# Misc.net
KiCad netlist of a schematic drawn in Altium Designer
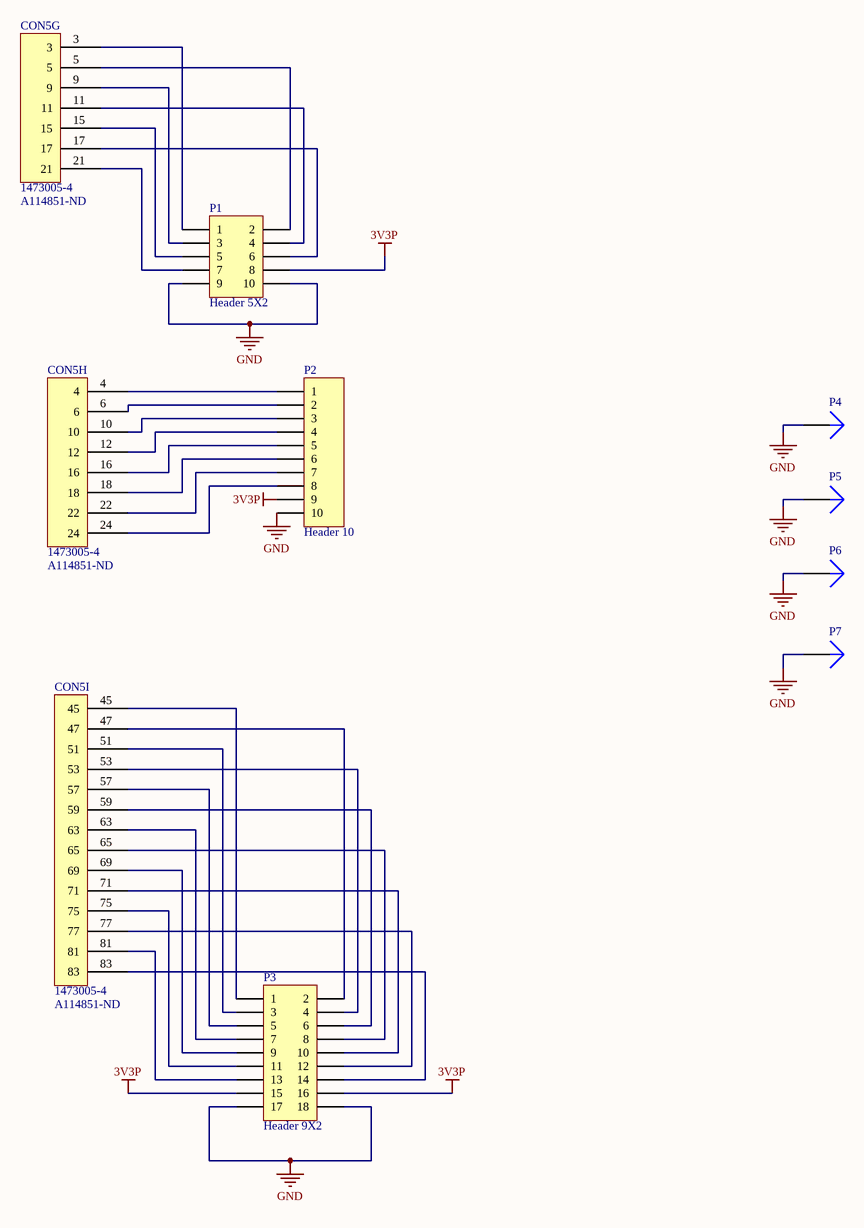
[diagram p0: Misc.SchDoc]

(export (version "E")
  (design (tool "Eeschema 10.0.6"))
  (components
    (comp (ref "CON5")
      (value "1473005-4")
      (footprint "SODIMM SOCKET .6 PITCH 200 POS RIGHT ANGLE")
      (fields
        (field (name "MANUFACTURER") "TE Connectivity (Tyco Electronics)")
        (field (name "SUPPLIER PART NUMBER 1") "A114851-ND")
      )
      (libsource (lib "RPIadaptor") (part "1473005-4"))
    )
    (comp (ref "P1")
      (value "Header 5X2")
      (footprint "HDR2X5")
      (description "Header, 5-Pin, Dual row")
      (fields (field (name "PUBLISHER") "Altium Limited"))
      (libsource (lib "Miscellaneous Connectors") (part "Header 5X2"))
    )
    (comp (ref "P2")
      (value "Header 10")
      (footprint "HDR1X10")
      (description "Header, 10-Pin")
      (fields (field (name "PUBLISHER") "Altium Limited"))
      (libsource (lib "Miscellaneous Connectors") (part "Header 10"))
    )
    (comp (ref "P3")
      (value "Header 9X2")
      (footprint "HDR2X9")
      (description "Header, 9-Pin, Dual row")
      (fields (field (name "PUBLISHER") "Altium Limited"))
      (libsource (lib "Miscellaneous Connectors") (part "Header 9X2"))
    )
    (comp (ref "P4")
      (value "Plug")
      (footprint "PIN1")
      (fields (field (name "PUBLISHER") "Altium Limited"))
      (libsource (lib "Miscellaneous Connectors") (part "Plug"))
    )
    (comp (ref "P5")
      (value "Plug")
      (footprint "PIN1")
      (fields (field (name "PUBLISHER") "Altium Limited"))
      (libsource (lib "Miscellaneous Connectors") (part "Plug"))
    )
    (comp (ref "P6")
      (value "Plug")
      (footprint "PIN1")
      (fields (field (name "PUBLISHER") "Altium Limited"))
      (libsource (lib "Miscellaneous Connectors") (part "Plug"))
    )
    (comp (ref "P7")
      (value "Plug")
      (footprint "PIN1")
      (fields (field (name "PUBLISHER") "Altium Limited"))
      (libsource (lib "Miscellaneous Connectors") (part "Plug"))
    )
  )
  (nets
    (net (code "1") (name "3V3P") (class "Default")
      (node (ref "P1") (pin "8") (pinfunction "8_8") (pintype "passive"))
      (node (ref "P2") (pin "9") (pinfunction "9_9") (pintype "passive"))
      (node (ref "P3") (pin "15") (pinfunction "15_15") (pintype "passive"))
      (node (ref "P3") (pin "16") (pinfunction "16_16") (pintype "passive"))
    )
    (net (code "2") (name "GND") (class "Default")
      (node (ref "P1") (pin "10") (pinfunction "10_10") (pintype "passive"))
      (node (ref "P1") (pin "9") (pinfunction "9_9") (pintype "passive"))
      (node (ref "P2") (pin "10") (pinfunction "10_10") (pintype "passive"))
      (node (ref "P3") (pin "17") (pinfunction "17_17") (pintype "passive"))
      (node (ref "P3") (pin "18") (pinfunction "18_18") (pintype "passive"))
      (node (ref "P4") (pin "1") (pinfunction "1_1") (pintype "passive"))
      (node (ref "P5") (pin "1") (pinfunction "1_1") (pintype "passive"))
      (node (ref "P6") (pin "1") (pinfunction "1_1") (pintype "passive"))
      (node (ref "P7") (pin "1") (pinfunction "1_1") (pintype "passive"))
    )
    (net (code "3") (name "Net-(CON5-Pad3)") (class "Default")
      (node (ref "CON5") (pin "3") (pinfunction "3_3") (pintype "passive"))
      (node (ref "P1") (pin "1") (pinfunction "1_1") (pintype "passive"))
    )
    (net (code "4") (name "Net-(CON5-Pad4)") (class "Default")
      (node (ref "CON5") (pin "4") (pinfunction "4_4") (pintype "passive"))
      (node (ref "P2") (pin "1") (pinfunction "1_1") (pintype "passive"))
    )
    (net (code "5") (name "Net-(CON5-Pad5)") (class "Default")
      (node (ref "CON5") (pin "5") (pinfunction "5_5") (pintype "passive"))
      (node (ref "P1") (pin "2") (pinfunction "2_2") (pintype "passive"))
    )
    (net (code "6") (name "Net-(CON5-Pad6)") (class "Default")
      (node (ref "CON5") (pin "6") (pinfunction "6_6") (pintype "passive"))
      (node (ref "P2") (pin "2") (pinfunction "2_2") (pintype "passive"))
    )
    (net (code "7") (name "Net-(CON5-Pad9)") (class "Default")
      (node (ref "CON5") (pin "9") (pinfunction "9_9") (pintype "passive"))
      (node (ref "P1") (pin "3") (pinfunction "3_3") (pintype "passive"))
    )
    (net (code "8") (name "Net-(CON5-Pad10)") (class "Default")
      (node (ref "CON5") (pin "10") (pinfunction "10_10") (pintype "passive"))
      (node (ref "P2") (pin "3") (pinfunction "3_3") (pintype "passive"))
    )
    (net (code "9") (name "Net-(CON5-Pad11)") (class "Default")
      (node (ref "CON5") (pin "11") (pinfunction "11_11") (pintype "passive"))
      (node (ref "P1") (pin "4") (pinfunction "4_4") (pintype "passive"))
    )
    (net (code "10") (name "Net-(CON5-Pad12)") (class "Default")
      (node (ref "CON5") (pin "12") (pinfunction "12_12") (pintype "passive"))
      (node (ref "P2") (pin "4") (pinfunction "4_4") (pintype "passive"))
    )
    (net (code "11") (name "Net-(CON5-Pad15)") (class "Default")
      (node (ref "CON5") (pin "15") (pinfunction "15_15") (pintype "passive"))
      (node (ref "P1") (pin "5") (pinfunction "5_5") (pintype "passive"))
    )
    (net (code "12") (name "Net-(CON5-Pad16)") (class "Default")
      (node (ref "CON5") (pin "16") (pinfunction "16_16") (pintype "passive"))
      (node (ref "P2") (pin "5") (pinfunction "5_5") (pintype "passive"))
    )
    (net (code "13") (name "Net-(CON5-Pad17)") (class "Default")
      (node (ref "CON5") (pin "17") (pinfunction "17_17") (pintype "passive"))
      (node (ref "P1") (pin "6") (pinfunction "6_6") (pintype "passive"))
    )
    (net (code "14") (name "Net-(CON5-Pad18)") (class "Default")
      (node (ref "CON5") (pin "18") (pinfunction "18_18") (pintype "passive"))
      (node (ref "P2") (pin "6") (pinfunction "6_6") (pintype "passive"))
    )
    (net (code "15") (name "Net-(CON5-Pad21)") (class "Default")
      (node (ref "CON5") (pin "21") (pinfunction "21_21") (pintype "passive"))
      (node (ref "P1") (pin "7") (pinfunction "7_7") (pintype "passive"))
    )
    (net (code "16") (name "Net-(CON5-Pad22)") (class "Default")
      (node (ref "CON5") (pin "22") (pinfunction "22_22") (pintype "passive"))
      (node (ref "P2") (pin "7") (pinfunction "7_7") (pintype "passive"))
    )
    (net (code "17") (name "Net-(CON5-Pad24)") (class "Default")
      (node (ref "CON5") (pin "24") (pinfunction "24_24") (pintype "passive"))
      (node (ref "P2") (pin "8") (pinfunction "8_8") (pintype "passive"))
    )
    (net (code "18") (name "Net-(CON5-Pad45)") (class "Default")
      (node (ref "CON5") (pin "45") (pinfunction "45_45") (pintype "passive"))
      (node (ref "P3") (pin "1") (pinfunction "1_1") (pintype "passive"))
    )
    (net (code "19") (name "Net-(CON5-Pad47)") (class "Default")
      (node (ref "CON5") (pin "47") (pinfunction "47_47") (pintype "passive"))
      (node (ref "P3") (pin "2") (pinfunction "2_2") (pintype "passive"))
    )
    (net (code "20") (name "Net-(CON5-Pad51)") (class "Default")
      (node (ref "CON5") (pin "51") (pinfunction "51_51") (pintype "passive"))
      (node (ref "P3") (pin "3") (pinfunction "3_3") (pintype "passive"))
    )
    (net (code "21") (name "Net-(CON5-Pad53)") (class "Default")
      (node (ref "CON5") (pin "53") (pinfunction "53_53") (pintype "passive"))
      (node (ref "P3") (pin "4") (pinfunction "4_4") (pintype "passive"))
    )
    (net (code "22") (name "Net-(CON5-Pad57)") (class "Default")
      (node (ref "CON5") (pin "57") (pinfunction "57_57") (pintype "passive"))
      (node (ref "P3") (pin "5") (pinfunction "5_5") (pintype "passive"))
    )
    (net (code "23") (name "Net-(CON5-Pad59)") (class "Default")
      (node (ref "CON5") (pin "59") (pinfunction "59_59") (pintype "passive"))
      (node (ref "P3") (pin "6") (pinfunction "6_6") (pintype "passive"))
    )
    (net (code "24") (name "Net-(CON5-Pad63)") (class "Default")
      (node (ref "CON5") (pin "63") (pinfunction "63_63") (pintype "passive"))
      (node (ref "P3") (pin "7") (pinfunction "7_7") (pintype "passive"))
    )
    (net (code "25") (name "Net-(CON5-Pad65)") (class "Default")
      (node (ref "CON5") (pin "65") (pinfunction "65_65") (pintype "passive"))
      (node (ref "P3") (pin "8") (pinfunction "8_8") (pintype "passive"))
    )
    (net (code "26") (name "Net-(CON5-Pad69)") (class "Default")
      (node (ref "CON5") (pin "69") (pinfunction "69_69") (pintype "passive"))
      (node (ref "P3") (pin "9") (pinfunction "9_9") (pintype "passive"))
    )
    (net (code "27") (name "Net-(CON5-Pad71)") (class "Default")
      (node (ref "CON5") (pin "71") (pinfunction "71_71") (pintype "passive"))
      (node (ref "P3") (pin "10") (pinfunction "10_10") (pintype "passive"))
    )
    (net (code "28") (name "Net-(CON5-Pad75)") (class "Default")
      (node (ref "CON5") (pin "75") (pinfunction "75_75") (pintype "passive"))
      (node (ref "P3") (pin "11") (pinfunction "11_11") (pintype "passive"))
    )
    (net (code "29") (name "Net-(CON5-Pad77)") (class "Default")
      (node (ref "CON5") (pin "77") (pinfunction "77_77") (pintype "passive"))
      (node (ref "P3") (pin "12") (pinfunction "12_12") (pintype "passive"))
    )
    (net (code "30") (name "Net-(CON5-Pad81)") (class "Default")
      (node (ref "CON5") (pin "81") (pinfunction "81_81") (pintype "passive"))
      (node (ref "P3") (pin "13") (pinfunction "13_13") (pintype "passive"))
    )
    (net (code "31") (name "Net-(CON5-Pad83)") (class "Default")
      (node (ref "CON5") (pin "83") (pinfunction "83_83") (pintype "passive"))
      (node (ref "P3") (pin "14") (pinfunction "14_14") (pintype "passive"))
    )
  )
)
